# 05_-_CPU_CRITICAL_SIGNALS.net
KiCad netlist of a schematic drawn in Altium Designer
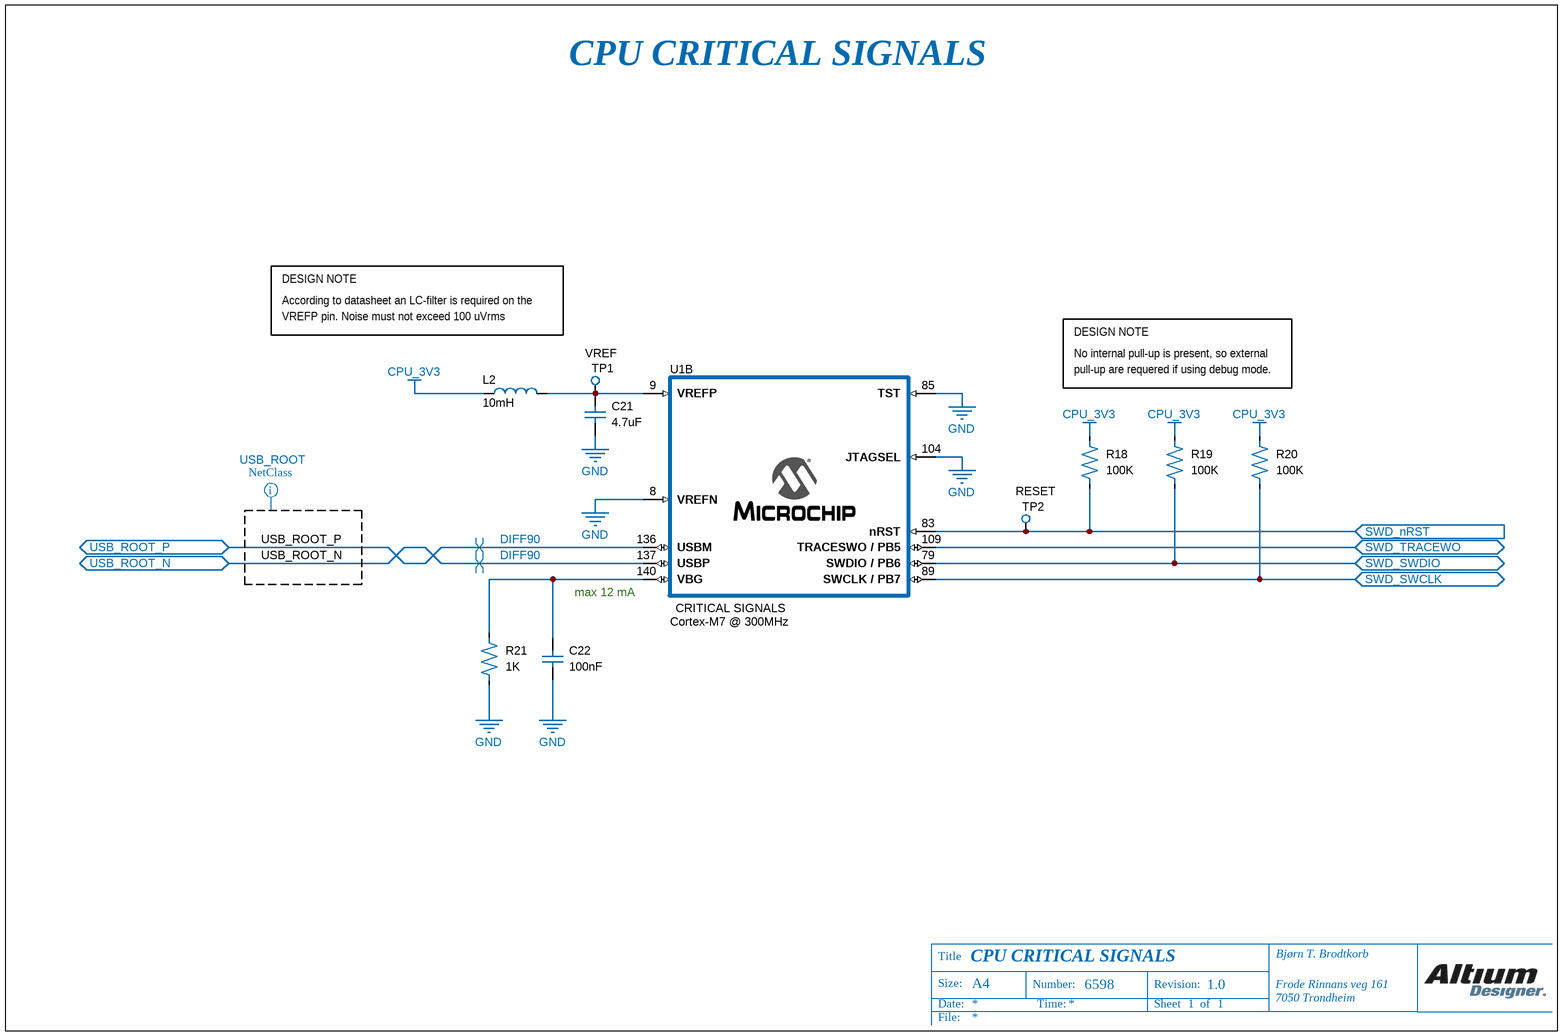
[diagram p0: [05] - CPU CRITICAL SIGNALS.SchDoc]

(export (version "E")
  (design (tool "Eeschema 10.0.6"))
  (components
    (comp (ref "C21")
      (value "4.7uF")
      (footprint "C0603")
      (description "C0603")
      (fields (field (name "Comment") "02016D104KAT2A"))
      (libsource (lib "Passive components") (part "02016D104KAT2A"))
    )
    (comp (ref "C22")
      (value "100nF")
      (footprint "C0402")
      (description "C0402")
      (fields (field (name "Comment") "04023C103KAT2A"))
      (libsource (lib "Passive components") (part "04023C103KAT2A"))
    )
    (comp (ref "L2")
      (value "10mH")
      (footprint "Inductor 0603")
      (description "Inductor 0603")
      (fields (field (name "Comment") "MLZ1608A2R2WT"))
      (libsource (lib "Passive components") (part "MLZ1608A2R2WT"))
    )
    (comp (ref "R18")
      (value "100K")
      (footprint "R0603")
      (description "R0603")
      (fields (field (name "Comment") "CPF-A-0603B100KE1"))
      (libsource (lib "Passive components") (part "CPF-A-0603B100KE1"))
    )
    (comp (ref "R19")
      (value "100K")
      (footprint "R0603")
      (description "R0603")
      (fields (field (name "Comment") "CPF-A-0603B100KE1"))
      (libsource (lib "Passive components") (part "CPF-A-0603B100KE1"))
    )
    (comp (ref "R20")
      (value "100K")
      (footprint "R0603")
      (description "R0603")
      (fields (field (name "Comment") "CPF-A-0603B100KE1"))
      (libsource (lib "Passive components") (part "CPF-A-0603B100KE1"))
    )
    (comp (ref "R21")
      (value "1K")
      (footprint "R0402")
      (description "R0402")
      (fields (field (name "Comment") "CRCW04020000Z0ED"))
      (libsource (lib "Passive components") (part "CRCW04020000Z0ED"))
    )
    (comp (ref "TP1")
      (value "Test point")
      (footprint "TEST POINT")
      (fields (field (name "TYPE") "VREF"))
      (libsource (lib "Miscellaneous") (part "Test point"))
    )
    (comp (ref "TP2")
      (value "Test point")
      (footprint "TEST POINT")
      (fields (field (name "TYPE") "RESET"))
      (libsource (lib "Miscellaneous") (part "Test point"))
    )
    (comp (ref "U1")
      (value "Cortex-M7 @ 300MHz")
      (footprint "ATSAMS70Q21A-AN")
      (description "ATSAMS70Q21")
      (libsource (lib "Microcontrollers") (part "ATSAMS70Q21A-AN"))
    )
  )
  (nets
    (net (code "1") (name "/SWD_SWCLK") (class "Default")
      (node (ref "R20") (pin "1") (pinfunction "1_1") (pintype "passive"))
      (node (ref "U1") (pin "89") (pinfunction "SWCLK_/_PB7_89") (pintype "bidirectional"))
    )
    (net (code "2") (name "/SWD_SWDIO") (class "Default")
      (node (ref "R19") (pin "1") (pinfunction "1_1") (pintype "passive"))
      (node (ref "U1") (pin "79") (pinfunction "SWDIO_/_PB6_79") (pintype "bidirectional"))
    )
    (net (code "3") (name "/SWD_TRACEWO") (class "Default")
      (node (ref "U1") (pin "109") (pinfunction "TRACESWO_/_PB5_109") (pintype "bidirectional"))
    )
    (net (code "4") (name "/SWD_nRST") (class "Default")
      (node (ref "R18") (pin "1") (pinfunction "1_1") (pintype "passive"))
      (node (ref "TP2") (pin "1") (pinfunction "33_1") (pintype "passive"))
      (node (ref "U1") (pin "83") (pinfunction "nRST_83") (pintype "input"))
    )
    (net (code "5") (name "/USB_ROOT_N") (class "Default")
      (node (ref "U1") (pin "137") (pinfunction "USBP_137") (pintype "bidirectional"))
    )
    (net (code "6") (name "/USB_ROOT_P") (class "Default")
      (node (ref "U1") (pin "136") (pinfunction "USBM_136") (pintype "bidirectional"))
    )
    (net (code "7") (name "CPU_3V3") (class "Default")
      (node (ref "L2") (pin "1") (pinfunction "1_1") (pintype "passive"))
      (node (ref "R18") (pin "2") (pinfunction "2_2") (pintype "passive"))
      (node (ref "R19") (pin "2") (pinfunction "2_2") (pintype "passive"))
      (node (ref "R20") (pin "2") (pinfunction "2_2") (pintype "passive"))
    )
    (net (code "8") (name "GND") (class "Default")
      (node (ref "C21") (pin "2") (pinfunction "2_2") (pintype "passive"))
      (node (ref "C22") (pin "1") (pinfunction "1_1") (pintype "passive"))
      (node (ref "R21") (pin "2") (pinfunction "3_2") (pintype "passive"))
      (node (ref "U1") (pin "104") (pinfunction "JTAGSEL_104") (pintype "input"))
      (node (ref "U1") (pin "8") (pinfunction "VREFN_8") (pintype "input"))
      (node (ref "U1") (pin "85") (pinfunction "TST_85") (pintype "input"))
    )
    (net (code "9") (name "Net-(TP1-33)") (class "Default")
      (node (ref "C21") (pin "1") (pinfunction "1_1") (pintype "passive"))
      (node (ref "L2") (pin "2") (pinfunction "2_2") (pintype "passive"))
      (node (ref "TP1") (pin "1") (pinfunction "33_1") (pintype "passive"))
      (node (ref "U1") (pin "9") (pinfunction "VREFP_9") (pintype "input"))
    )
    (net (code "10") (name "Net-(U1B-VBG)") (class "Default")
      (node (ref "C22") (pin "2") (pinfunction "2_2") (pintype "passive"))
      (node (ref "R21") (pin "1") (pinfunction "1_1") (pintype "passive"))
      (node (ref "U1") (pin "140") (pinfunction "VBG_140") (pintype "bidirectional"))
    )
  )
)
